# discoball-v2.net
KiCad netlist of a schematic drawn in EAGLE
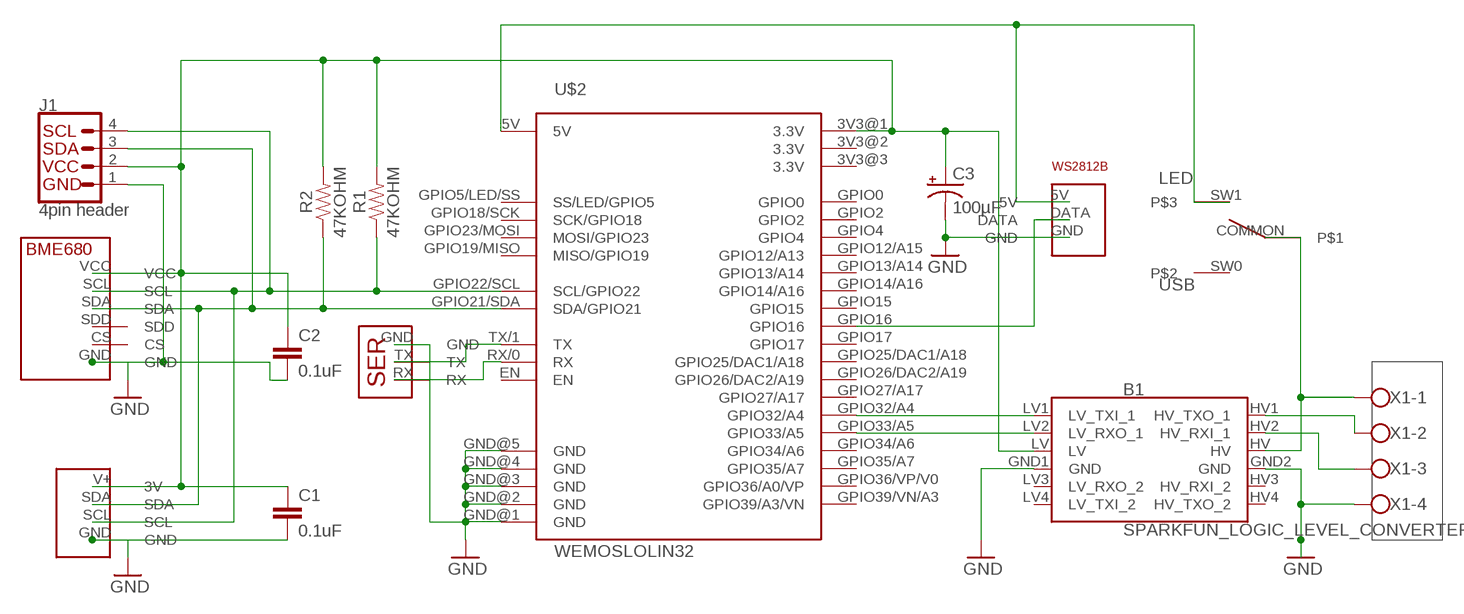
[diagram p0: schematic, sheet 1]

(export (version "E")
  (design (tool "Eeschema 10.0.6"))
  (components
    (comp (ref "B1")
      (value "SPARKFUN_LOGIC_LEVEL_CONVERTER")
      (footprint "eagle-import:SPARKFUN_LOGIC_LEVEL_CONVERTER")
      (libsource (lib "eagle-import") (part "SPARKFUN_LOGIC_LEVEL_CONVERTER"))
    )
    (comp (ref "C1")
      (value "0.1uF")
      (footprint "eagle-import:CAP-PTH-SMALL-KIT")
      (libsource (lib "eagle-import") (part "0.1UF-KIT-EZ-50V-20%"))
    )
    (comp (ref "C2")
      (value "0.1uF")
      (footprint "eagle-import:CAP-PTH-SMALL-KIT")
      (libsource (lib "eagle-import") (part "0.1UF-KIT-EZ-50V-20%"))
    )
    (comp (ref "C3")
      (value "100µF")
      (footprint "eagle-import:CPOL-RADIAL-100UF-25V")
      (libsource (lib "eagle-import") (part "CAP_POLPTH1"))
    )
    (comp (ref "J1")
      (value "4pin header")
      (footprint "eagle-import:1X04_1MM_RA")
      (libsource (lib "eagle-import") (part "QWIIC_CONNECTORJS-1MM"))
    )
    (comp (ref "R1")
      (value "47KOHM")
      (footprint "eagle-import:AXIAL-0.3-KIT")
      (libsource (lib "eagle-import") (part "47KOHM"))
    )
    (comp (ref "R2")
      (value "47KOHM")
      (footprint "eagle-import:AXIAL-0.3-KIT")
      (libsource (lib "eagle-import") (part "47KOHM"))
    )
    (comp (ref "U$1")
      (value "BME680BREAKOUT")
      (footprint "eagle-import:BME680BREAKOUT")
      (libsource (lib "eagle-import") (part "BME680BREAKOUT"))
    )
    (comp (ref "U$2")
      (value "WEMOSLOLIN32")
      (footprint "eagle-import:LOLIN32VAR1")
      (libsource (lib "eagle-import") (part "WEMOSLOLIN32"))
    )
    (comp (ref "U$3")
      (value "I2CHEADER")
      (footprint "eagle-import:I2CHEADER")
      (libsource (lib "eagle-import") (part "I2CHEADER"))
    )
    (comp (ref "U$4")
      (value "SPDTSWITCH")
      (footprint "eagle-import:SPDTSWITCH")
      (libsource (lib "eagle-import") (part "SPDTSWITCH"))
    )
    (comp (ref "U$6")
      (value "SERIALHEADER")
      (footprint "eagle-import:SERIALHEADER")
      (libsource (lib "eagle-import") (part "SERIALHEADER"))
    )
    (comp (ref "U$7")
      (value "WS2812BHEADER")
      (footprint "eagle-import:WS2812BHEADER")
      (libsource (lib "eagle-import") (part "WS2812BHEADER"))
    )
    (comp (ref "X1")
      (value "W237-4")
      (footprint "eagle-import:W237-4")
      (libsource (lib "eagle-import") (part "W237-4"))
    )
  )
  (nets
    (net (code "1") (name "/3.3V") (class "Default")
      (node (ref "U$2") (pin "3V3@3") (pinfunction "3.3V_3V3@3") (pintype "power_in"))
    )
    (net (code "2") (name "GND") (class "Default")
      (node (ref "B1") (pin "GND1") (pinfunction "GND_GND1") (pintype "power_in"))
      (node (ref "B1") (pin "GND2") (pinfunction "GND_GND2") (pintype "power_in"))
      (node (ref "C1") (pin "2") (pinfunction "2_2") (pintype "passive"))
      (node (ref "C2") (pin "2") (pinfunction "2_2") (pintype "passive"))
      (node (ref "C3") (pin "2") (pinfunction "-_2") (pintype "passive"))
      (node (ref "J1") (pin "1") (pinfunction "GND_1") (pintype "power_in"))
      (node (ref "U$1") (pin "GND") (pinfunction "GND_GND") (pintype "power_in"))
      (node (ref "U$2") (pin "GND@1") (pinfunction "GND_GND@1") (pintype "power_in"))
      (node (ref "U$2") (pin "GND@2") (pinfunction "GND_GND@2") (pintype "bidirectional"))
      (node (ref "U$2") (pin "GND@3") (pinfunction "GND_GND@3") (pintype "bidirectional"))
      (node (ref "U$2") (pin "GND@4") (pinfunction "GND_GND@4") (pintype "bidirectional"))
      (node (ref "U$2") (pin "GND@5") (pinfunction "GND_GND@5") (pintype "bidirectional"))
      (node (ref "U$3") (pin "GND") (pinfunction "GND_GND") (pintype "power_in"))
      (node (ref "U$6") (pin "GND") (pinfunction "GND_GND") (pintype "power_in"))
      (node (ref "U$7") (pin "GND") (pinfunction "GND_GND") (pintype "power_in"))
      (node (ref "X1") (pin "4") (pinfunction "KL_4") (pintype "passive"))
    )
    (net (code "3") (name "Net-(B1-HV_RXI_1)") (class "Default")
      (node (ref "B1") (pin "HV2") (pinfunction "HV_RXI_1_HV2") (pintype "bidirectional"))
      (node (ref "X1") (pin "3") (pinfunction "KL_3") (pintype "passive"))
    )
    (net (code "4") (name "Net-(B1-HV_TXO_1)") (class "Default")
      (node (ref "B1") (pin "HV1") (pinfunction "HV_TXO_1_HV1") (pintype "bidirectional"))
      (node (ref "X1") (pin "2") (pinfunction "KL_2") (pintype "passive"))
    )
    (net (code "5") (name "Net-(B1-LV_RXO_1)") (class "Default")
      (node (ref "B1") (pin "LV2") (pinfunction "LV_RXO_1_LV2") (pintype "bidirectional"))
      (node (ref "U$2") (pin "GPIO33/A5") (pinfunction "GPIO33/A5_GPIO33/A5") (pintype "bidirectional"))
    )
    (net (code "6") (name "Net-(B1-LV_TXI_1)") (class "Default")
      (node (ref "B1") (pin "LV1") (pinfunction "LV_TXI_1_LV1") (pintype "bidirectional"))
      (node (ref "U$2") (pin "GPIO32/A4") (pinfunction "GPIO32/A4_GPIO32/A4") (pintype "bidirectional"))
    )
    (net (code "7") (name "Net-(C3-+)") (class "Default")
      (node (ref "B1") (pin "LV") (pinfunction "LV_LV") (pintype "power_in"))
      (node (ref "C1") (pin "1") (pinfunction "1_1") (pintype "passive"))
      (node (ref "C2") (pin "1") (pinfunction "1_1") (pintype "passive"))
      (node (ref "C3") (pin "1") (pinfunction "+_1") (pintype "passive"))
      (node (ref "J1") (pin "2") (pinfunction "VCC_2") (pintype "power_in"))
      (node (ref "R1") (pin "P$2") (pinfunction "2_P$2") (pintype "passive"))
      (node (ref "R2") (pin "P$2") (pinfunction "2_P$2") (pintype "passive"))
      (node (ref "U$1") (pin "VCC") (pinfunction "VCC_VCC") (pintype "power_in"))
      (node (ref "U$2") (pin "3V3@1") (pinfunction "3.3V_3V3@1") (pintype "bidirectional"))
      (node (ref "U$3") (pin "V+") (pinfunction "3V_V+") (pintype "power_in"))
    )
    (net (code "8") (name "Net-(J1-SCL)") (class "Default")
      (node (ref "J1") (pin "4") (pinfunction "SCL_4") (pintype "passive"))
      (node (ref "R1") (pin "P$1") (pinfunction "1_P$1") (pintype "passive"))
      (node (ref "U$1") (pin "SCL") (pinfunction "SCL_SCL") (pintype "bidirectional"))
      (node (ref "U$2") (pin "GPIO22/SCL") (pinfunction "SCL/GPIO22_GPIO22/SCL") (pintype "bidirectional"))
      (node (ref "U$3") (pin "SCL") (pinfunction "SCL_SCL") (pintype "bidirectional"))
    )
    (net (code "9") (name "Net-(J1-SDA)") (class "Default")
      (node (ref "J1") (pin "3") (pinfunction "SDA_3") (pintype "passive"))
      (node (ref "R2") (pin "P$1") (pinfunction "1_P$1") (pintype "passive"))
      (node (ref "U$1") (pin "SDA") (pinfunction "SDA_SDA") (pintype "bidirectional"))
      (node (ref "U$2") (pin "GPIO21/SDA") (pinfunction "SDA/GPIO21_GPIO21/SDA") (pintype "bidirectional"))
      (node (ref "U$3") (pin "SDA") (pinfunction "SDA_SDA") (pintype "bidirectional"))
    )
    (net (code "10") (name "Net-(U$2-PadGPIO16)") (class "Default")
      (node (ref "U$2") (pin "GPIO16") (pinfunction "GPIO16_GPIO16") (pintype "bidirectional"))
      (node (ref "U$7") (pin "DATA") (pinfunction "DATA_DATA") (pintype "bidirectional"))
    )
    (net (code "11") (name "Net-(U$2-RX)") (class "Default")
      (node (ref "U$2") (pin "RX/0") (pinfunction "RX_RX/0") (pintype "input"))
      (node (ref "U$6") (pin "RX") (pinfunction "RX_RX") (pintype "input"))
    )
    (net (code "12") (name "Net-(U$2-TX)") (class "Default")
      (node (ref "U$2") (pin "TX/1") (pinfunction "TX_TX/1") (pintype "output"))
      (node (ref "U$6") (pin "TX") (pinfunction "TX_TX") (pintype "output"))
    )
    (net (code "13") (name "Net-(U$4-P$1)") (class "Default")
      (node (ref "B1") (pin "HV") (pinfunction "HV_HV") (pintype "power_in"))
      (node (ref "U$4") (pin "COMMON") (pinfunction "P$1_COMMON") (pintype "bidirectional"))
      (node (ref "X1") (pin "1") (pinfunction "KL_1") (pintype "passive"))
    )
    (net (code "14") (name "Net-(U$4-P$3)") (class "Default")
      (node (ref "U$2") (pin "5V") (pinfunction "5V_5V") (pintype "power_in"))
      (node (ref "U$4") (pin "SW1") (pinfunction "P$3_SW1") (pintype "bidirectional"))
      (node (ref "U$7") (pin "5V") (pinfunction "5V_5V") (pintype "power_in"))
    )
    (net (code "15") (name "unconnected-(B1-HV_RXI_2-PadHV3)") (class "Default")
      (node (ref "B1") (pin "HV3") (pinfunction "HV_RXI_2_HV3") (pintype "bidirectional"))
    )
    (net (code "16") (name "unconnected-(B1-HV_TXO_2-PadHV4)") (class "Default")
      (node (ref "B1") (pin "HV4") (pinfunction "HV_TXO_2_HV4") (pintype "bidirectional"))
    )
    (net (code "17") (name "unconnected-(B1-LV_RXO_2-PadLV3)") (class "Default")
      (node (ref "B1") (pin "LV3") (pinfunction "LV_RXO_2_LV3") (pintype "bidirectional"))
    )
    (net (code "18") (name "unconnected-(B1-LV_TXI_2-PadLV4)") (class "Default")
      (node (ref "B1") (pin "LV4") (pinfunction "LV_TXI_2_LV4") (pintype "bidirectional"))
    )
    (net (code "19") (name "unconnected-(U$1-PadCS)") (class "Default")
      (node (ref "U$1") (pin "CS") (pinfunction "CS_CS") (pintype "bidirectional"))
    )
    (net (code "20") (name "unconnected-(U$1-PadSDD)") (class "Default")
      (node (ref "U$1") (pin "SDD") (pinfunction "SDD_SDD") (pintype "bidirectional"))
    )
    (net (code "21") (name "unconnected-(U$2-3.3V-Pad3V3@2)") (class "Default")
      (node (ref "U$2") (pin "3V3@2") (pinfunction "3.3V_3V3@2") (pintype "bidirectional"))
    )
    (net (code "22") (name "unconnected-(U$2-GPIO12{slash}A13-PadGPIO12{slash}A15)") (class "Default")
      (node (ref "U$2") (pin "GPIO12/A15") (pinfunction "GPIO12/A13_GPIO12/A15") (pintype "bidirectional"))
    )
    (net (code "23") (name "unconnected-(U$2-GPIO36{slash}A0{slash}VP-PadGPIO36{slash}VP{slash}V0)") (class "Default")
      (node (ref "U$2") (pin "GPIO36/VP/V0") (pinfunction "GPIO36/A0/VP_GPIO36/VP/V0") (pintype "bidirectional"))
    )
    (net (code "24") (name "unconnected-(U$2-GPIO39{slash}A3{slash}VN-PadGPIO39{slash}VN{slash}A3)") (class "Default")
      (node (ref "U$2") (pin "GPIO39/VN/A3") (pinfunction "GPIO39/A3/VN_GPIO39/VN/A3") (pintype "bidirectional"))
    )
    (net (code "25") (name "unconnected-(U$2-MISO{slash}GPIO19-PadGPIO19{slash}MISO)") (class "Default")
      (node (ref "U$2") (pin "GPIO19/MISO") (pinfunction "MISO/GPIO19_GPIO19/MISO") (pintype "bidirectional"))
    )
    (net (code "26") (name "unconnected-(U$2-MOSI{slash}GPIO23-PadGPIO23{slash}MOSI)") (class "Default")
      (node (ref "U$2") (pin "GPIO23/MOSI") (pinfunction "MOSI/GPIO23_GPIO23/MOSI") (pintype "bidirectional"))
    )
    (net (code "27") (name "unconnected-(U$2-PadEN)") (class "Default")
      (node (ref "U$2") (pin "EN") (pinfunction "EN_EN") (pintype "bidirectional"))
    )
    (net (code "28") (name "unconnected-(U$2-PadGPIO0)") (class "Default")
      (node (ref "U$2") (pin "GPIO0") (pinfunction "GPIO0_GPIO0") (pintype "bidirectional"))
    )
    (net (code "29") (name "unconnected-(U$2-PadGPIO2)") (class "Default")
      (node (ref "U$2") (pin "GPIO2") (pinfunction "GPIO2_GPIO2") (pintype "bidirectional"))
    )
    (net (code "30") (name "unconnected-(U$2-PadGPIO4)") (class "Default")
      (node (ref "U$2") (pin "GPIO4") (pinfunction "GPIO4_GPIO4") (pintype "bidirectional"))
    )
    (net (code "31") (name "unconnected-(U$2-PadGPIO13{slash}A14)") (class "Default")
      (node (ref "U$2") (pin "GPIO13/A14") (pinfunction "GPIO13/A14_GPIO13/A14") (pintype "bidirectional"))
    )
    (net (code "32") (name "unconnected-(U$2-PadGPIO14{slash}A16)") (class "Default")
      (node (ref "U$2") (pin "GPIO14/A16") (pinfunction "GPIO14/A16_GPIO14/A16") (pintype "bidirectional"))
    )
    (net (code "33") (name "unconnected-(U$2-PadGPIO15)") (class "Default")
      (node (ref "U$2") (pin "GPIO15") (pinfunction "GPIO15_GPIO15") (pintype "bidirectional"))
    )
    (net (code "34") (name "unconnected-(U$2-PadGPIO17)") (class "Default")
      (node (ref "U$2") (pin "GPIO17") (pinfunction "GPIO17_GPIO17") (pintype "bidirectional"))
    )
    (net (code "35") (name "unconnected-(U$2-PadGPIO25{slash}DAC1{slash}A18)") (class "Default")
      (node (ref "U$2") (pin "GPIO25/DAC1/A18") (pinfunction "GPIO25/DAC1/A18_GPIO25/DAC1/A18") (pintype "bidirectional"))
    )
    (net (code "36") (name "unconnected-(U$2-PadGPIO26{slash}DAC2{slash}A19)") (class "Default")
      (node (ref "U$2") (pin "GPIO26/DAC2/A19") (pinfunction "GPIO26/DAC2/A19_GPIO26/DAC2/A19") (pintype "bidirectional"))
    )
    (net (code "37") (name "unconnected-(U$2-PadGPIO27{slash}A17)") (class "Default")
      (node (ref "U$2") (pin "GPIO27/A17") (pinfunction "GPIO27/A17_GPIO27/A17") (pintype "bidirectional"))
    )
    (net (code "38") (name "unconnected-(U$2-PadGPIO34{slash}A6)") (class "Default")
      (node (ref "U$2") (pin "GPIO34/A6") (pinfunction "GPIO34/A6_GPIO34/A6") (pintype "bidirectional"))
    )
    (net (code "39") (name "unconnected-(U$2-PadGPIO35{slash}A7)") (class "Default")
      (node (ref "U$2") (pin "GPIO35/A7") (pinfunction "GPIO35/A7_GPIO35/A7") (pintype "bidirectional"))
    )
    (net (code "40") (name "unconnected-(U$2-SCK{slash}GPIO18-PadGPIO18{slash}SCK)") (class "Default")
      (node (ref "U$2") (pin "GPIO18/SCK") (pinfunction "SCK/GPIO18_GPIO18/SCK") (pintype "bidirectional"))
    )
    (net (code "41") (name "unconnected-(U$2-SS{slash}LED{slash}GPIO5-PadGPIO5{slash}LED{slash}SS)") (class "Default")
      (node (ref "U$2") (pin "GPIO5/LED/SS") (pinfunction "SS/LED/GPIO5_GPIO5/LED/SS") (pintype "bidirectional"))
    )
    (net (code "42") (name "unconnected-(U$4-P$2-PadSW0)") (class "Default")
      (node (ref "U$4") (pin "SW0") (pinfunction "P$2_SW0") (pintype "bidirectional"))
    )
  )
)
